# top_hk2.net
KiCad netlist of a schematic drawn in EAGLE
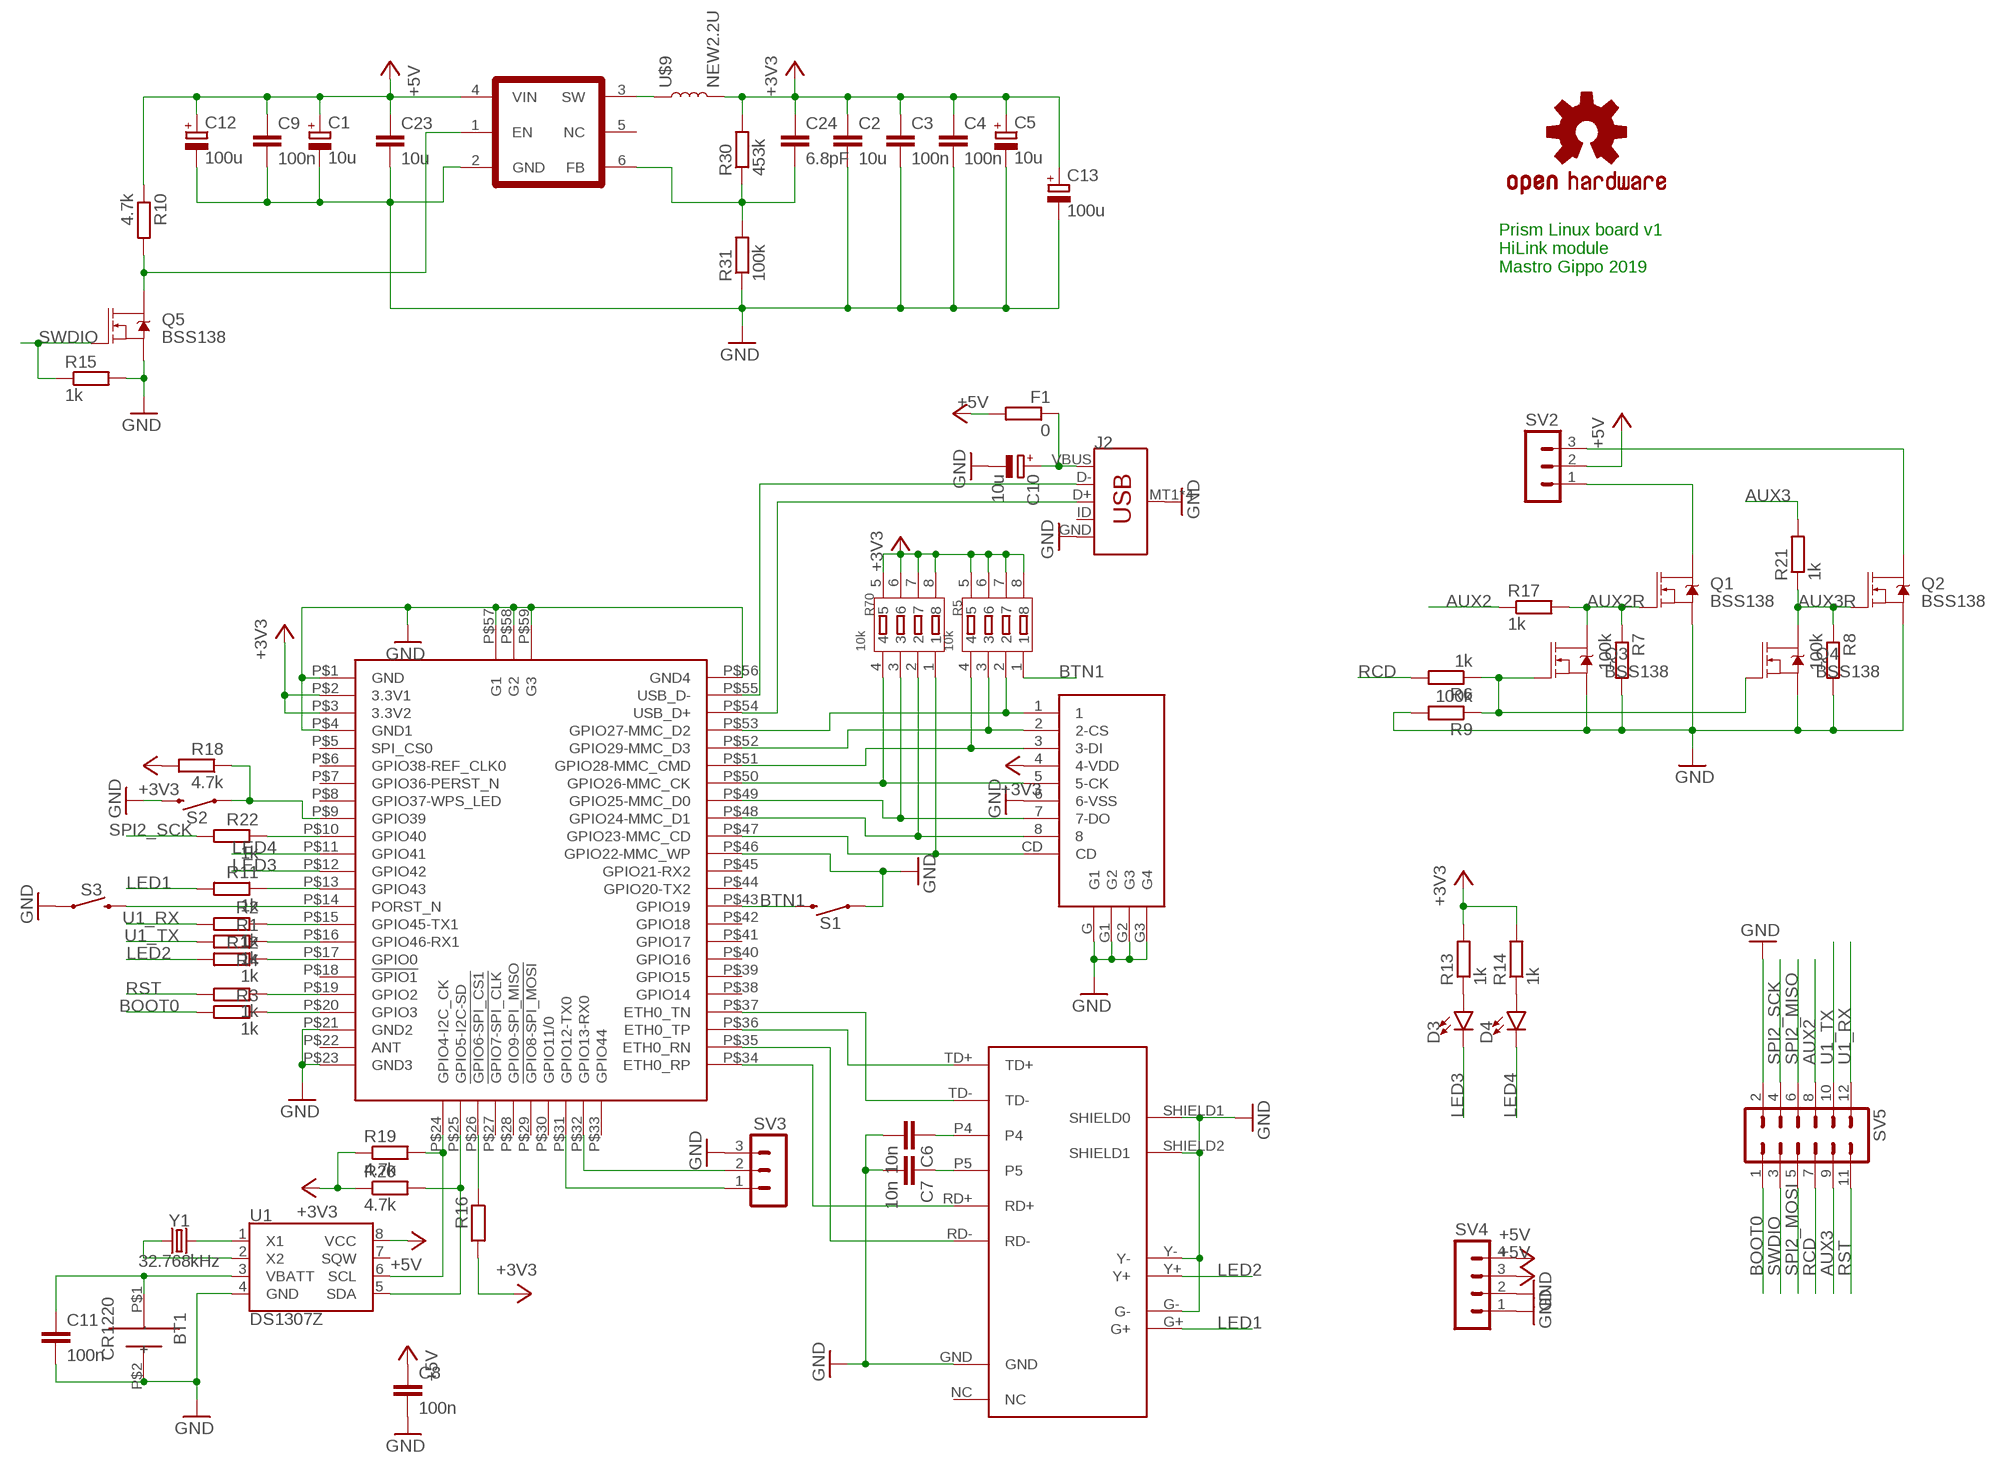
[diagram p0: schematic, sheet 1]

(export (version "E")
  (design (tool "Eeschema 10.0.6"))
  (components
    (comp (ref "BT1")
      (value "CR1220")
      (footprint "eagle-import:CR1220")
      (libsource (lib "eagle-import") (part "CR1220"))
    )
    (comp (ref "C1")
      (value "10u")
      (footprint "eagle-import:B_3528-21R")
      (libsource (lib "eagle-import") (part "CPOL-EUB/3528-21R"))
    )
    (comp (ref "C2")
      (value "10u")
      (footprint "eagle-import:C0805K")
      (libsource (lib "eagle-import") (part "C-EUC0805K"))
    )
    (comp (ref "C3")
      (value "100n")
      (footprint "eagle-import:C0805K")
      (libsource (lib "eagle-import") (part "C-EUC0805K"))
    )
    (comp (ref "C4")
      (value "100n")
      (footprint "eagle-import:C0805K")
      (libsource (lib "eagle-import") (part "C-EUC0805K"))
    )
    (comp (ref "C5")
      (value "10u")
      (footprint "eagle-import:B_3528-21R")
      (libsource (lib "eagle-import") (part "CPOL-EUB/3528-21R"))
    )
    (comp (ref "C6")
      (value "10n")
      (footprint "eagle-import:C0805K")
      (libsource (lib "eagle-import") (part "C-EUC0805K"))
    )
    (comp (ref "C7")
      (value "10n")
      (footprint "eagle-import:C0805K")
      (libsource (lib "eagle-import") (part "C-EUC0805K"))
    )
    (comp (ref "C8")
      (value "100n")
      (footprint "eagle-import:C0805K")
      (libsource (lib "eagle-import") (part "C-EUC0805K"))
    )
    (comp (ref "C9")
      (value "100n")
      (footprint "eagle-import:C0805K")
      (libsource (lib "eagle-import") (part "C-EUC0805K"))
    )
    (comp (ref "C10")
      (value "10u")
      (footprint "eagle-import:B_3528-21R")
      (libsource (lib "eagle-import") (part "CPOL-EUB/3528-21R"))
    )
    (comp (ref "C11")
      (value "100n")
      (footprint "eagle-import:C0805K")
      (libsource (lib "eagle-import") (part "C-EUC0805K"))
    )
    (comp (ref "C12")
      (value "100u")
      (footprint "eagle-import:153CLV-0505")
      (libsource (lib "eagle-import") (part "CPOL-EU153CLV-0505"))
    )
    (comp (ref "C13")
      (value "100u")
      (footprint "eagle-import:153CLV-0505")
      (libsource (lib "eagle-import") (part "CPOL-EU153CLV-0505"))
    )
    (comp (ref "C23")
      (value "10u")
      (footprint "eagle-import:C0805K")
      (libsource (lib "eagle-import") (part "C-EUC0805K"))
    )
    (comp (ref "C24")
      (value "6.8pF")
      (footprint "eagle-import:C0805K")
      (libsource (lib "eagle-import") (part "C-EUC0805K"))
    )
    (comp (ref "D3")
      (value "LED1206")
      (footprint "eagle-import:LED-1206")
      (libsource (lib "eagle-import") (part "LED1206"))
    )
    (comp (ref "D4")
      (value "LED1206")
      (footprint "eagle-import:LED-1206")
      (libsource (lib "eagle-import") (part "LED1206"))
    )
    (comp (ref "F1")
      (value "0")
      (footprint "eagle-import:R0603")
      (libsource (lib "eagle-import") (part "R-EU_R0603"))
    )
    (comp (ref "J2")
      (value "USB_MICRO-B_SMT")
      (footprint "eagle-import:USB-MICROB")
      (libsource (lib "eagle-import") (part "USB_MICRO-B_SMT"))
    )
    (comp (ref "Q1")
      (value "BSS138")
      (footprint "eagle-import:SOT23-3")
      (libsource (lib "eagle-import") (part "MOSFET-NCH-BSS138"))
    )
    (comp (ref "Q2")
      (value "BSS138")
      (footprint "eagle-import:SOT23-3")
      (libsource (lib "eagle-import") (part "MOSFET-NCH-BSS138"))
    )
    (comp (ref "Q3")
      (value "BSS138")
      (footprint "eagle-import:SOT23-3")
      (libsource (lib "eagle-import") (part "MOSFET-NCH-BSS138"))
    )
    (comp (ref "Q4")
      (value "BSS138")
      (footprint "eagle-import:SOT23-3")
      (libsource (lib "eagle-import") (part "MOSFET-NCH-BSS138"))
    )
    (comp (ref "Q5")
      (value "BSS138")
      (footprint "eagle-import:SOT23-3")
      (libsource (lib "eagle-import") (part "MOSFET-NCH-BSS138"))
    )
    (comp (ref "R1")
      (value "1k")
      (footprint "eagle-import:R0805")
      (libsource (lib "eagle-import") (part "R-EU_R0805"))
    )
    (comp (ref "R2")
      (value "1k")
      (footprint "eagle-import:R0805")
      (libsource (lib "eagle-import") (part "R-EU_R0805"))
    )
    (comp (ref "R3")
      (value "1k")
      (footprint "eagle-import:R0805")
      (libsource (lib "eagle-import") (part "R-EU_R0805"))
    )
    (comp (ref "R4")
      (value "1k")
      (footprint "eagle-import:R0805")
      (libsource (lib "eagle-import") (part "R-EU_R0805"))
    )
    (comp (ref "R5")
      (value "10k")
      (footprint "eagle-import:RA1206-8")
      (fields (field (name "MPN") "Chip-Array-Series-1%"))
      (libsource (lib "eagle-import") (part "SMD-RES-ARRAY-1K-4R(RA1206-8)"))
    )
    (comp (ref "R6")
      (value "1k")
      (footprint "eagle-import:R0805")
      (libsource (lib "eagle-import") (part "R-EU_R0805"))
    )
    (comp (ref "R7")
      (value "100k")
      (footprint "eagle-import:R0805")
      (libsource (lib "eagle-import") (part "R-EU_R0805"))
    )
    (comp (ref "R8")
      (value "100k")
      (footprint "eagle-import:R0805")
      (libsource (lib "eagle-import") (part "R-EU_R0805"))
    )
    (comp (ref "R9")
      (value "100k")
      (footprint "eagle-import:R0805")
      (libsource (lib "eagle-import") (part "R-EU_R0805"))
    )
    (comp (ref "R10")
      (value "4.7k")
      (footprint "eagle-import:R0805")
      (libsource (lib "eagle-import") (part "R-EU_R0805"))
    )
    (comp (ref "R11")
      (value "1k")
      (footprint "eagle-import:R0805")
      (libsource (lib "eagle-import") (part "R-EU_R0805"))
    )
    (comp (ref "R12")
      (value "1k")
      (footprint "eagle-import:R0805")
      (libsource (lib "eagle-import") (part "R-EU_R0805"))
    )
    (comp (ref "R13")
      (value "1k")
      (footprint "eagle-import:R0805")
      (libsource (lib "eagle-import") (part "R-EU_R0805"))
    )
    (comp (ref "R14")
      (value "1k")
      (footprint "eagle-import:R0805")
      (libsource (lib "eagle-import") (part "R-EU_R0805"))
    )
    (comp (ref "R15")
      (value "1k")
      (footprint "eagle-import:R0805")
      (libsource (lib "eagle-import") (part "R-EU_R0805"))
    )
    (comp (ref "R16")
      (value "R-EU_R0805")
      (footprint "eagle-import:R0805")
      (libsource (lib "eagle-import") (part "R-EU_R0805"))
    )
    (comp (ref "R17")
      (value "1k")
      (footprint "eagle-import:R0805")
      (libsource (lib "eagle-import") (part "R-EU_R0805"))
    )
    (comp (ref "R18")
      (value "4.7k")
      (footprint "eagle-import:R0805")
      (libsource (lib "eagle-import") (part "R-EU_R0805"))
    )
    (comp (ref "R19")
      (value "4.7k")
      (footprint "eagle-import:R0805")
      (libsource (lib "eagle-import") (part "R-EU_R0805"))
    )
    (comp (ref "R20")
      (value "4.7k")
      (footprint "eagle-import:R0805")
      (libsource (lib "eagle-import") (part "R-EU_R0805"))
    )
    (comp (ref "R21")
      (value "1k")
      (footprint "eagle-import:R0805")
      (libsource (lib "eagle-import") (part "R-EU_R0805"))
    )
    (comp (ref "R22")
      (value "1k")
      (footprint "eagle-import:R0805")
      (libsource (lib "eagle-import") (part "R-EU_R0805"))
    )
    (comp (ref "R30")
      (value "453k")
      (footprint "eagle-import:R0805")
      (libsource (lib "eagle-import") (part "R_EU"))
    )
    (comp (ref "R31")
      (value "100k")
      (footprint "eagle-import:R0805")
      (libsource (lib "eagle-import") (part "R_EU"))
    )
    (comp (ref "R70")
      (value "10k")
      (footprint "eagle-import:RA1206-8")
      (fields (field (name "MPN") "Chip-Array-Series-1%"))
      (libsource (lib "eagle-import") (part "SMD-RES-ARRAY-1K-4R(RA1206-8)"))
    )
    (comp (ref "S1")
      (value "MOMENTARY-SWITCH-SPST-SMD-6.0X3.5MM")
      (footprint "eagle-import:TACTILE_SWITCH_SMD_6.0X3.5MM")
      (libsource (lib "eagle-import") (part "MOMENTARY-SWITCH-SPST-SMD-6.0X3.5MM"))
    )
    (comp (ref "S2")
      (value "MOMENTARY-SWITCH-SPST-SMD-6.0X3.5MM")
      (footprint "eagle-import:TACTILE_SWITCH_SMD_6.0X3.5MM")
      (libsource (lib "eagle-import") (part "MOMENTARY-SWITCH-SPST-SMD-6.0X3.5MM"))
    )
    (comp (ref "S3")
      (value "MOMENTARY-SWITCH-SPST-PTH-RIGHT-ANGLE")
      (footprint "eagle-import:TACTILE_SWITCH_PTH_RIGHT_ANGLE")
      (libsource (lib "eagle-import") (part "MOMENTARY-SWITCH-SPST-PTH-RIGHT-ANGLE"))
    )
    (comp (ref "SV2")
      (value "MA03-1")
      (footprint "eagle-import:MA03-1")
      (libsource (lib "eagle-import") (part "MA03-1"))
    )
    (comp (ref "SV3")
      (value "MA03-1")
      (footprint "eagle-import:MA03-1")
      (libsource (lib "eagle-import") (part "MA03-1"))
    )
    (comp (ref "SV4")
      (value "MA04-1")
      (footprint "eagle-import:MA04-1")
      (libsource (lib "eagle-import") (part "MA04-1"))
    )
    (comp (ref "SV5")
      (value "MA06-2")
      (footprint "eagle-import:MA06-2")
      (libsource (lib "eagle-import") (part "MA06-2"))
    )
    (comp (ref "U$1")
      (value "OSHW-LOGOS")
      (footprint "eagle-import:OSHW-LOGO-S")
      (libsource (lib "eagle-import") (part "OSHW-LOGOS"))
    )
    (comp (ref "U$2")
      (value "HLK-7688A")
      (footprint "eagle-import:HLK-7688A")
      (libsource (lib "eagle-import") (part "HLK-7688A"))
    )
    (comp (ref "U$3")
      (value "MICRO_SD")
      (footprint "eagle-import:MICRO_SD_C")
      (libsource (lib "eagle-import") (part "MICRO_SD"))
    )
    (comp (ref "U$4")
      (value "HR911105A")
      (footprint "eagle-import:RJ45")
      (libsource (lib "eagle-import") (part "HR911105A"))
    )
    (comp (ref "U$8")
      (value "TLV62658")
      (footprint "eagle-import:SOT23-6")
      (libsource (lib "eagle-import") (part "TLV62658"))
    )
    (comp (ref "U$9")
      (value "NEW2.2U")
      (footprint "eagle-import:INDUCTOR_4X4MM")
      (libsource (lib "eagle-import") (part "NEW2.2U"))
    )
    (comp (ref "U1")
      (value "DS1307Z")
      (footprint "eagle-import:SO08-0.15")
      (libsource (lib "eagle-import") (part "DS1307Z"))
    )
    (comp (ref "Y1")
      (value "32.768kHz")
      (footprint "eagle-import:CRYSTAL-SMD-2X6-CYL")
      (libsource (lib "eagle-import") (part "CRYSTAL-32.768KHZSMD-2X6"))
    )
  )
  (nets
    (net (code "1") (name "+3V3") (class "Default")
      (node (ref "C13") (pin "+") (pinfunction "+_+") (pintype "passive"))
      (node (ref "C2") (pin "1") (pinfunction "1_1") (pintype "passive"))
      (node (ref "C24") (pin "1") (pinfunction "1_1") (pintype "passive"))
      (node (ref "C3") (pin "1") (pinfunction "1_1") (pintype "passive"))
      (node (ref "C4") (pin "1") (pinfunction "1_1") (pintype "passive"))
      (node (ref "C5") (pin "+") (pinfunction "+_+") (pintype "passive"))
      (node (ref "R13") (pin "2") (pinfunction "2_2") (pintype "passive"))
      (node (ref "R14") (pin "2") (pinfunction "2_2") (pintype "passive"))
      (node (ref "R16") (pin "2") (pinfunction "2_2") (pintype "passive"))
      (node (ref "R18") (pin "2") (pinfunction "2_2") (pintype "passive"))
      (node (ref "R19") (pin "1") (pinfunction "1_1") (pintype "passive"))
      (node (ref "R20") (pin "1") (pinfunction "1_1") (pintype "passive"))
      (node (ref "R30") (pin "2") (pinfunction "2_2") (pintype "passive"))
      (node (ref "R5") (pin "5") (pinfunction "5_5") (pintype "bidirectional"))
      (node (ref "R5") (pin "6") (pinfunction "6_6") (pintype "bidirectional"))
      (node (ref "R5") (pin "7") (pinfunction "7_7") (pintype "bidirectional"))
      (node (ref "R5") (pin "8") (pinfunction "8_8") (pintype "bidirectional"))
      (node (ref "R70") (pin "5") (pinfunction "5_5") (pintype "bidirectional"))
      (node (ref "R70") (pin "6") (pinfunction "6_6") (pintype "bidirectional"))
      (node (ref "R70") (pin "7") (pinfunction "7_7") (pintype "bidirectional"))
      (node (ref "R70") (pin "8") (pinfunction "8_8") (pintype "bidirectional"))
      (node (ref "U$2") (pin "P$2") (pinfunction "3.3V1_P$2") (pintype "bidirectional"))
      (node (ref "U$2") (pin "P$3") (pinfunction "3.3V2_P$3") (pintype "bidirectional"))
      (node (ref "U$3") (pin "4") (pinfunction "4-VDD_4") (pintype "bidirectional"))
      (node (ref "U$9") (pin "P$2") (pinfunction "2_P$2") (pintype "passive"))
    )
    (net (code "2") (name "+5V") (class "Default")
      (node (ref "C1") (pin "+") (pinfunction "+_+") (pintype "passive"))
      (node (ref "C12") (pin "+") (pinfunction "+_+") (pintype "passive"))
      (node (ref "C23") (pin "1") (pinfunction "1_1") (pintype "passive"))
      (node (ref "C8") (pin "1") (pinfunction "1_1") (pintype "passive"))
      (node (ref "C9") (pin "1") (pinfunction "1_1") (pintype "passive"))
      (node (ref "F1") (pin "2") (pinfunction "2_2") (pintype "passive"))
      (node (ref "R10") (pin "1") (pinfunction "1_1") (pintype "passive"))
      (node (ref "SV2") (pin "2") (pinfunction "2_2") (pintype "passive"))
      (node (ref "SV4") (pin "3") (pinfunction "3_3") (pintype "passive"))
      (node (ref "SV4") (pin "4") (pinfunction "4_4") (pintype "passive"))
      (node (ref "U$8") (pin "4") (pinfunction "VIN_4") (pintype "bidirectional"))
      (node (ref "U1") (pin "8") (pinfunction "VCC_8") (pintype "bidirectional"))
    )
    (net (code "3") (name "/AUX2") (class "Default")
      (node (ref "R17") (pin "1") (pinfunction "1_1") (pintype "passive"))
      (node (ref "SV5") (pin "8") (pinfunction "8_8") (pintype "passive"))
    )
    (net (code "4") (name "/AUX2R") (class "Default")
      (node (ref "Q1") (pin "1") (pinfunction "G_1") (pintype "bidirectional"))
      (node (ref "Q3") (pin "3") (pinfunction "D_3") (pintype "bidirectional"))
      (node (ref "R17") (pin "2") (pinfunction "2_2") (pintype "passive"))
      (node (ref "R7") (pin "1") (pinfunction "1_1") (pintype "passive"))
    )
    (net (code "5") (name "/AUX3") (class "Default")
      (node (ref "R21") (pin "2") (pinfunction "2_2") (pintype "passive"))
      (node (ref "SV5") (pin "9") (pinfunction "9_9") (pintype "passive"))
    )
    (net (code "6") (name "/AUX3R") (class "Default")
      (node (ref "Q2") (pin "1") (pinfunction "G_1") (pintype "bidirectional"))
      (node (ref "Q4") (pin "3") (pinfunction "D_3") (pintype "bidirectional"))
      (node (ref "R21") (pin "1") (pinfunction "1_1") (pintype "passive"))
      (node (ref "R8") (pin "1") (pinfunction "1_1") (pintype "passive"))
    )
    (net (code "7") (name "/BOOT0") (class "Default")
      (node (ref "R3") (pin "2") (pinfunction "2_2") (pintype "passive"))
      (node (ref "SV5") (pin "1") (pinfunction "1_1") (pintype "passive"))
    )
    (net (code "8") (name "/BTN1") (class "Default")
      (node (ref "R5") (pin "1") (pinfunction "1_1") (pintype "bidirectional"))
      (node (ref "S1") (pin "2") (pinfunction "2_2") (pintype "passive"))
      (node (ref "U$2") (pin "P$43") (pinfunction "GPIO19_P$43") (pintype "bidirectional"))
    )
    (net (code "9") (name "/LED1") (class "Default")
      (node (ref "R11") (pin "2") (pinfunction "2_2") (pintype "passive"))
      (node (ref "U$4") (pin "G+") (pinfunction "G+_G+") (pintype "bidirectional"))
    )
    (net (code "10") (name "/LED2") (class "Default")
      (node (ref "R12") (pin "2") (pinfunction "2_2") (pintype "passive"))
      (node (ref "U$4") (pin "Y+") (pinfunction "Y+_Y+") (pintype "bidirectional"))
    )
    (net (code "11") (name "/LED3") (class "Default")
      (node (ref "D3") (pin "C") (pinfunction "C_C") (pintype "passive"))
      (node (ref "U$2") (pin "P$12") (pinfunction "GPIO42_P$12") (pintype "bidirectional"))
    )
    (net (code "12") (name "/LED4") (class "Default")
      (node (ref "D4") (pin "C") (pinfunction "C_C") (pintype "passive"))
      (node (ref "U$2") (pin "P$11") (pinfunction "GPIO41_P$11") (pintype "bidirectional"))
    )
    (net (code "13") (name "/RCD") (class "Default")
      (node (ref "R6") (pin "2") (pinfunction "2_2") (pintype "passive"))
      (node (ref "SV5") (pin "7") (pinfunction "7_7") (pintype "passive"))
    )
    (net (code "14") (name "/RST") (class "Default")
      (node (ref "R4") (pin "2") (pinfunction "2_2") (pintype "passive"))
      (node (ref "SV5") (pin "11") (pinfunction "11_11") (pintype "passive"))
    )
    (net (code "15") (name "/SPI2_MISO") (class "Default")
      (node (ref "SV5") (pin "6") (pinfunction "6_6") (pintype "passive"))
    )
    (net (code "16") (name "/SPI2_MOSI") (class "Default")
      (node (ref "SV5") (pin "5") (pinfunction "5_5") (pintype "passive"))
    )
    (net (code "17") (name "/SPI2_SCK") (class "Default")
      (node (ref "R22") (pin "2") (pinfunction "2_2") (pintype "passive"))
      (node (ref "SV5") (pin "4") (pinfunction "4_4") (pintype "passive"))
    )
    (net (code "18") (name "/SWDIO") (class "Default")
      (node (ref "Q5") (pin "1") (pinfunction "G_1") (pintype "bidirectional"))
      (node (ref "R15") (pin "1") (pinfunction "1_1") (pintype "passive"))
      (node (ref "SV5") (pin "3") (pinfunction "3_3") (pintype "passive"))
    )
    (net (code "19") (name "/U1_RX") (class "Default")
      (node (ref "R2") (pin "2") (pinfunction "2_2") (pintype "passive"))
      (node (ref "SV5") (pin "12") (pinfunction "12_12") (pintype "passive"))
    )
    (net (code "20") (name "/U1_TX") (class "Default")
      (node (ref "R1") (pin "2") (pinfunction "2_2") (pintype "passive"))
      (node (ref "SV5") (pin "10") (pinfunction "10_10") (pintype "passive"))
    )
    (net (code "21") (name "GND") (class "Default")
      (node (ref "BT1") (pin "P$2") (pinfunction "-_P$2") (pintype "power_in"))
      (node (ref "C1") (pin "-") (pinfunction "-_-") (pintype "passive"))
      (node (ref "C10") (pin "-") (pinfunction "-_-") (pintype "passive"))
      (node (ref "C11") (pin "2") (pinfunction "2_2") (pintype "passive"))
      (node (ref "C12") (pin "-") (pinfunction "-_-") (pintype "passive"))
      (node (ref "C13") (pin "-") (pinfunction "-_-") (pintype "passive"))
      (node (ref "C2") (pin "2") (pinfunction "2_2") (pintype "passive"))
      (node (ref "C23") (pin "2") (pinfunction "2_2") (pintype "passive"))
      (node (ref "C3") (pin "2") (pinfunction "2_2") (pintype "passive"))
      (node (ref "C4") (pin "2") (pinfunction "2_2") (pintype "passive"))
      (node (ref "C5") (pin "-") (pinfunction "-_-") (pintype "passive"))
      (node (ref "C6") (pin "2") (pinfunction "2_2") (pintype "passive"))
      (node (ref "C7") (pin "2") (pinfunction "2_2") (pintype "passive"))
      (node (ref "C8") (pin "2") (pinfunction "2_2") (pintype "passive"))
      (node (ref "C9") (pin "2") (pinfunction "2_2") (pintype "passive"))
      (node (ref "J2") (pin "GND") (pinfunction "GND_GND") (pintype "power_in"))
      (node (ref "J2") (pin "MT1") (pinfunction "SHIELD_MT1") (pintype "bidirectional"))
      (node (ref "J2") (pin "MT2") (pinfunction "SHIELD_MT2") (pintype "bidirectional"))
      (node (ref "J2") (pin "P$1") (pinfunction "SHIELD_P$1") (pintype "bidirectional"))
      (node (ref "J2") (pin "P$2") (pinfunction "SHIELD_P$2") (pintype "bidirectional"))
      (node (ref "Q1") (pin "2") (pinfunction "S_2") (pintype "bidirectional"))
      (node (ref "Q2") (pin "2") (pinfunction "S_2") (pintype "bidirectional"))
      (node (ref "Q3") (pin "2") (pinfunction "S_2") (pintype "bidirectional"))
      (node (ref "Q4") (pin "2") (pinfunction "S_2") (pintype "bidirectional"))
      (node (ref "Q5") (pin "2") (pinfunction "S_2") (pintype "bidirectional"))
      (node (ref "R15") (pin "2") (pinfunction "2_2") (pintype "passive"))
      (node (ref "R31") (pin "1") (pinfunction "1_1") (pintype "passive"))
      (node (ref "R7") (pin "2") (pinfunction "2_2") (pintype "passive"))
      (node (ref "R8") (pin "2") (pinfunction "2_2") (pintype "passive"))
      (node (ref "R9") (pin "2") (pinfunction "2_2") (pintype "passive"))
      (node (ref "S1") (pin "1") (pinfunction "1_1") (pintype "passive"))
      (node (ref "S2") (pin "2") (pinfunction "2_2") (pintype "passive"))
      (node (ref "S3") (pin "1") (pinfunction "1_1") (pintype "passive"))
      (node (ref "SV3") (pin "3") (pinfunction "3_3") (pintype "passive"))
      (node (ref "SV4") (pin "1") (pinfunction "1_1") (pintype "passive"))
      (node (ref "SV4") (pin "2") (pinfunction "2_2") (pintype "passive"))
      (node (ref "SV5") (pin "2") (pinfunction "2_2") (pintype "passive"))
      (node (ref "U$2") (pin "P$1") (pinfunction "GND_P$1") (pintype "bidirectional"))
      (node (ref "U$2") (pin "P$21") (pinfunction "GND2_P$21") (pintype "bidirectional"))
      (node (ref "U$2") (pin "P$23") (pinfunction "GND3_P$23") (pintype "bidirectional"))
      (node (ref "U$2") (pin "P$4") (pinfunction "GND1_P$4") (pintype "bidirectional"))
      (node (ref "U$2") (pin "P$46") (pinfunction "GPIO22-MMC_WP_P$46") (pintype "bidirectional"))
      (node (ref "U$2") (pin "P$56") (pinfunction "GND4_P$56") (pintype "bidirectional"))
      (node (ref "U$2") (pin "P$57") (pinfunction "G1_P$57") (pintype "bidirectional"))
      (node (ref "U$2") (pin "P$58") (pinfunction "G2_P$58") (pintype "bidirectional"))
      (node (ref "U$2") (pin "P$59") (pinfunction "G3_P$59") (pintype "bidirectional"))
      (node (ref "U$3") (pin "6") (pinfunction "6-VSS_6") (pintype "bidirectional"))
      (node (ref "U$3") (pin "G") (pinfunction "G1_G") (pintype "bidirectional"))
      (node (ref "U$3") (pin "G1") (pinfunction "G2_G1") (pintype "bidirectional"))
      (node (ref "U$3") (pin "G2") (pinfunction "G3_G2") (pintype "bidirectional"))
      (node (ref "U$3") (pin "G3") (pinfunction "G4_G3") (pintype "bidirectional"))
      (node (ref "U$4") (pin "G-") (pinfunction "G-_G-") (pintype "bidirectional"))
      (node (ref "U$4") (pin "GND") (pinfunction "GND_GND") (pintype "bidirectional"))
      (node (ref "U$4") (pin "SHIELD1") (pinfunction "SHIELD0_SHIELD1") (pintype "bidirectional"))
      (node (ref "U$4") (pin "SHIELD2") (pinfunction "SHIELD1_SHIELD2") (pintype "bidirectional"))
      (node (ref "U$4") (pin "Y-") (pinfunction "Y-_Y-") (pintype "bidirectional"))
      (node (ref "U$8") (pin "2") (pinfunction "GND_2") (pintype "bidirectional"))
      (node (ref "U1") (pin "4") (pinfunction "GND_4") (pintype "bidirectional"))
    )
    (net (code "22") (name "Net-(BT1-+)") (class "Default")
      (node (ref "BT1") (pin "P$1") (pinfunction "+_P$1") (pintype "power_in"))
      (node (ref "C11") (pin "1") (pinfunction "1_1") (pintype "passive"))
      (node (ref "U1") (pin "3") (pinfunction "VBATT_3") (pintype "bidirectional"))
    )
    (net (code "23") (name "Net-(C6-Pad1)") (class "Default")
      (node (ref "C6") (pin "1") (pinfunction "1_1") (pintype "passive"))
      (node (ref "U$4") (pin "P4") (pinfunction "P4_P4") (pintype "bidirectional"))
    )
    (net (code "24") (name "Net-(C7-Pad1)") (class "Default")
      (node (ref "C7") (pin "1") (pinfunction "1_1") (pintype "passive"))
      (node (ref "U$4") (pin "P5") (pinfunction "P5_P5") (pintype "bidirectional"))
    )
    (net (code "25") (name "Net-(C10-Pad+)") (class "Default")
      (node (ref "C10") (pin "+") (pinfunction "+_+") (pintype "passive"))
      (node (ref "F1") (pin "1") (pinfunction "1_1") (pintype "passive"))
      (node (ref "J2") (pin "VBUS") (pinfunction "VBUS_VBUS") (pintype "power_in"))
    )
    (net (code "26") (name "Net-(D3-PadA)") (class "Default")
      (node (ref "D3") (pin "A") (pinfunction "A_A") (pintype "passive"))
      (node (ref "R13") (pin "1") (pinfunction "1_1") (pintype "passive"))
    )
    (net (code "27") (name "Net-(D4-PadA)") (class "Default")
      (node (ref "D4") (pin "A") (pinfunction "A_A") (pintype "passive"))
      (node (ref "R14") (pin "1") (pinfunction "1_1") (pintype "passive"))
    )
    (net (code "28") (name "Net-(Q1-D)") (class "Default")
      (node (ref "Q1") (pin "3") (pinfunction "D_3") (pintype "bidirectional"))
      (node (ref "SV2") (pin "1") (pinfunction "1_1") (pintype "passive"))
    )
    (net (code "29") (name "Net-(Q2-D)") (class "Default")
      (node (ref "Q2") (pin "3") (pinfunction "D_3") (pintype "bidirectional"))
      (node (ref "SV2") (pin "3") (pinfunction "3_3") (pintype "passive"))
    )
    (net (code "30") (name "Net-(Q3-G)") (class "Default")
      (node (ref "Q3") (pin "1") (pinfunction "G_1") (pintype "bidirectional"))
      (node (ref "Q4") (pin "1") (pinfunction "G_1") (pintype "bidirectional"))
      (node (ref "R6") (pin "1") (pinfunction "1_1") (pintype "passive"))
      (node (ref "R9") (pin "1") (pinfunction "1_1") (pintype "passive"))
    )
    (net (code "31") (name "Net-(Q5-D)") (class "Default")
      (node (ref "Q5") (pin "3") (pinfunction "D_3") (pintype "bidirectional"))
      (node (ref "R10") (pin "2") (pinfunction "2_2") (pintype "passive"))
      (node (ref "U$8") (pin "1") (pinfunction "EN_1") (pintype "bidirectional"))
    )
    (net (code "32") (name "Net-(U$2-ETH0_RN)") (class "Default")
      (node (ref "U$2") (pin "P$35") (pinfunction "ETH0_RN_P$35") (pintype "bidirectional"))
      (node (ref "U$4") (pin "RD-") (pinfunction "RD-_RD-") (pintype "bidirectional"))
    )
    (net (code "33") (name "Net-(U$2-ETH0_RP)") (class "Default")
      (node (ref "U$2") (pin "P$34") (pinfunction "ETH0_RP_P$34") (pintype "bidirectional"))
      (node (ref "U$4") (pin "RD+") (pinfunction "RD+_RD+") (pintype "bidirectional"))
    )
    (net (code "34") (name "Net-(U$2-ETH0_TN)") (class "Default")
      (node (ref "U$2") (pin "P$37") (pinfunction "ETH0_TN_P$37") (pintype "bidirectional"))
      (node (ref "U$4") (pin "TD-") (pinfunction "TD-_TD-") (pintype "bidirectional"))
    )
    (net (code "35") (name "Net-(U$2-ETH0_TP)") (class "Default")
      (node (ref "U$2") (pin "P$36") (pinfunction "ETH0_TP_P$36") (pintype "bidirectional"))
      (node (ref "U$4") (pin "TD+") (pinfunction "TD+_TD+") (pintype "bidirectional"))
    )
    (net (code "36") (name "Net-(U$2-GPIO0)") (class "Default")
      (node (ref "R12") (pin "1") (pinfunction "1_1") (pintype "passive"))
      (node (ref "U$2") (pin "P$17") (pinfunction "GPIO0_P$17") (pintype "bidirectional"))
    )
    (net (code "37") (name "Net-(U$2-GPIO2)") (class "Default")
      (node (ref "R4") (pin "1") (pinfunction "1_1") (pintype "passive"))
      (node (ref "U$2") (pin "P$19") (pinfunction "GPIO2_P$19") (pintype "bidirectional"))
    )
    (net (code "38") (name "Net-(U$2-GPIO3)") (class "Default")
      (node (ref "R3") (pin "1") (pinfunction "1_1") (pintype "passive"))
      (node (ref "U$2") (pin "P$20") (pinfunction "GPIO3_P$20") (pintype "bidirectional"))
    )
    (net (code "39") (name "Net-(U$2-GPIO4-I2C_CK)") (class "Default")
      (node (ref "R19") (pin "2") (pinfunction "2_2") (pintype "passive"))
      (node (ref "U$2") (pin "P$24") (pinfunction "GPIO4-I2C_CK_P$24") (pintype "bidirectional"))
      (node (ref "U1") (pin "6") (pinfunction "SCL_6") (pintype "bidirectional"))
    )
    (net (code "40") (name "Net-(U$2-GPIO5-I2C-SD)") (class "Default")
      (node (ref "R20") (pin "2") (pinfunction "2_2") (pintype "passive"))
      (node (ref "U$2") (pin "P$25") (pinfunction "GPIO5-I2C-SD_P$25") (pintype "bidirectional"))
      (node (ref "U1") (pin "5") (pinfunction "SDA_5") (pintype "bidirectional"))
    )
    (net (code "41") (name "Net-(U$2-GPIO12-TX0)") (class "Default")
      (node (ref "SV3") (pin "1") (pinfunction "1_1") (pintype "passive"))
      (node (ref "U$2") (pin "P$31") (pinfunction "GPIO12-TX0_P$31") (pintype "bidirectional"))
    )
    (net (code "42") (name "Net-(U$2-GPIO13-RX0)") (class "Default")
      (node (ref "SV3") (pin "2") (pinfunction "2_2") (pintype "passive"))
      (node (ref "U$2") (pin "P$32") (pinfunction "GPIO13-RX0_P$32") (pintype "bidirectional"))
    )
    (net (code "43") (name "Net-(U$2-GPIO23-MMC_CD)") (class "Default")
      (node (ref "R70") (pin "1") (pinfunction "1_1") (pintype "bidirectional"))
      (node (ref "U$2") (pin "P$47") (pinfunction "GPIO23-MMC_CD_P$47") (pintype "bidirectional"))
      (node (ref "U$3") (pin "CD") (pinfunction "CD_CD") (pintype "bidirectional"))
    )
    (net (code "44") (name "Net-(U$2-GPIO24-MMC_D1)") (class "Default")
      (node (ref "R70") (pin "2") (pinfunction "2_2") (pintype "bidirectional"))
      (node (ref "U$2") (pin "P$48") (pinfunction "GPIO24-MMC_D1_P$48") (pintype "bidirectional"))
      (node (ref "U$3") (pin "8") (pinfunction "8_8") (pintype "bidirectional"))
    )
    (net (code "45") (name "Net-(U$2-GPIO25-MMC_D0)") (class "Default")
      (node (ref "R70") (pin "3") (pinfunction "3_3") (pintype "bidirectional"))
      (node (ref "U$2") (pin "P$49") (pinfunction "GPIO25-MMC_D0_P$49") (pintype "bidirectional"))
      (node (ref "U$3") (pin "7") (pinfunction "7-DO_7") (pintype "bidirectional"))
    )
    (net (code "46") (name "Net-(U$2-GPIO26-MMC_CK)") (class "Default")
      (node (ref "R70") (pin "4") (pinfunction "4_4") (pintype "bidirectional"))
      (node (ref "U$2") (pin "P$50") (pinfunction "GPIO26-MMC_CK_P$50") (pintype "bidirectional"))
      (node (ref "U$3") (pin "5") (pinfunction "5-CK_5") (pintype "bidirectional"))
    )
    (net (code "47") (name "Net-(U$2-GPIO27-MMC_D2)") (class "Default")
      (node (ref "R5") (pin "2") (pinfunction "2_2") (pintype "bidirectional"))
      (node (ref "U$2") (pin "P$53") (pinfunction "GPIO27-MMC_D2_P$53") (pintype "bidirectional"))
      (node (ref "U$3") (pin "1") (pinfunction "1_1") (pintype "bidirectional"))
    )
    (net (code "48") (name "Net-(U$2-GPIO28-MMC_CMD)") (class "Default")
      (node (ref "R5") (pin "4") (pinfunction "4_4") (pintype "bidirectional"))
      (node (ref "U$2") (pin "P$51") (pinfunction "GPIO28-MMC_CMD_P$51") (pintype "bidirectional"))
      (node (ref "U$3") (pin "3") (pinfunction "3-DI_3") (pintype "bidirectional"))
    )
    (net (code "49") (name "Net-(U$2-GPIO29-MMC_D3)") (class "Default")
      (node (ref "R5") (pin "3") (pinfunction "3_3") (pintype "bidirectional"))
      (node (ref "U$2") (pin "P$52") (pinfunction "GPIO29-MMC_D3_P$52") (pintype "bidirectional"))
      (node (ref "U$3") (pin "2") (pinfunction "2-CS_2") (pintype "bidirectional"))
    )
    (net (code "50") (name "Net-(U$2-GPIO39)") (class "Default")
      (node (ref "R18") (pin "1") (pinfunction "1_1") (pintype "passive"))
      (node (ref "S2") (pin "1") (pinfunction "1_1") (pintype "passive"))
      (node (ref "U$2") (pin "P$9") (pinfunction "GPIO39_P$9") (pintype "bidirectional"))
    )
    (net (code "51") (name "Net-(U$2-GPIO40)") (class "Default")
      (node (ref "R22") (pin "1") (pinfunction "1_1") (pintype "passive"))
      (node (ref "U$2") (pin "P$10") (pinfunction "GPIO40_P$10") (pintype "bidirectional"))
    )
    (net (code "52") (name "Net-(U$2-GPIO43)") (class "Default")
      (node (ref "R11") (pin "1") (pinfunction "1_1") (pintype "passive"))
      (node (ref "U$2") (pin "P$13") (pinfunction "GPIO43_P$13") (pintype "bidirectional"))
    )
    (net (code "53") (name "Net-(U$2-GPIO45-TX1)") (class "Default")
      (node (ref "R2") (pin "1") (pinfunction "1_1") (pintype "passive"))
      (node (ref "U$2") (pin "P$15") (pinfunction "GPIO45-TX1_P$15") (pintype "bidirectional"))
    )
    (net (code "54") (name "Net-(U$2-GPIO46-RX1)") (class "Default")
      (node (ref "R1") (pin "1") (pinfunction "1_1") (pintype "passive"))
      (node (ref "U$2") (pin "P$16") (pinfunction "GPIO46-RX1_P$16") (pintype "bidirectional"))
    )
    (net (code "55") (name "Net-(U$2-PORST_N)") (class "Default")
      (node (ref "S3") (pin "2") (pinfunction "2_2") (pintype "passive"))
      (node (ref "U$2") (pin "P$14") (pinfunction "PORST_N_P$14") (pintype "bidirectional"))
    )
    (net (code "56") (name "Net-(U$2-USB_D+)") (class "Default")
      (node (ref "J2") (pin "D+") (pinfunction "D+_D+") (pintype "bidirectional"))
      (node (ref "U$2") (pin "P$54") (pinfunction "USB_D+_P$54") (pintype "bidirectional"))
    )
    (net (code "57") (name "Net-(U$2-USB_D-)") (class "Default")
      (node (ref "J2") (pin "D-") (pinfunction "D-_D-") (pintype "bidirectional"))
      (node (ref "U$2") (pin "P$55") (pinfunction "USB_D-_P$55") (pintype "bidirectional"))
    )
    (net (code "58") (name "Net-(U$2-~{GPIO6-SPI_CS1})") (class "Default")
      (node (ref "R16") (pin "1") (pinfunction "1_1") (pintype "passive"))
      (node (ref "U$2") (pin "P$26") (pinfunction "~{GPIO6-SPI_CS1}_P$26") (pintype "bidirectional"))
    )
    (net (code "59") (name "Net-(U$8-FB)") (class "Default")
      (node (ref "C24") (pin "2") (pinfunction "2_2") (pintype "passive"))
      (node (ref "R30") (pin "1") (pinfunction "1_1") (pintype "passive"))
      (node (ref "R31") (pin "2") (pinfunction "2_2") (pintype "passive"))
      (node (ref "U$8") (pin "6") (pinfunction "FB_6") (pintype "bidirectional"))
    )
    (net (code "60") (name "Net-(U$8-SW)") (class "Default")
      (node (ref "U$8") (pin "3") (pinfunction "SW_3") (pintype "bidirectional"))
      (node (ref "U$9") (pin "P$1") (pinfunction "1_P$1") (pintype "passive"))
    )
    (net (code "61") (name "Net-(U1-X1)") (class "Default")
      (node (ref "U1") (pin "1") (pinfunction "X1_1") (pintype "bidirectional"))
      (node (ref "Y1") (pin "X2") (pinfunction "2_X2") (pintype "passive"))
    )
    (net (code "62") (name "Net-(U1-X2)") (class "Default")
      (node (ref "U1") (pin "2") (pinfunction "X2_2") (pintype "bidirectional"))
      (node (ref "Y1") (pin "X1") (pinfunction "1_X1") (pintype "passive"))
    )
    (net (code "63") (name "unconnected-(J2-PadID)") (class "Default")
      (node (ref "J2") (pin "ID") (pinfunction "ID_ID") (pintype "bidirectional"))
    )
    (net (code "64") (name "unconnected-(U$2-ANT-PadP$22)") (class "Default")
      (node (ref "U$2") (pin "P$22") (pinfunction "ANT_P$22") (pintype "bidirectional"))
    )
    (net (code "65") (name "unconnected-(U$2-GPIO9-SPI_MISO-PadP$28)") (class "Default")
      (node (ref "U$2") (pin "P$28") (pinfunction "GPIO9-SPI_MISO_P$28") (pintype "bidirectional"))
    )
    (net (code "66") (name "unconnected-(U$2-GPIO11{slash}0-PadP$30)") (class "Default")
      (node (ref "U$2") (pin "P$30") (pinfunction "GPIO11/0_P$30") (pintype "bidirectional"))
    )
    (net (code "67") (name "unconnected-(U$2-GPIO14-PadP$38)") (class "Default")
      (node (ref "U$2") (pin "P$38") (pinfunction "GPIO14_P$38") (pintype "bidirectional"))
    )
    (net (code "68") (name "unconnected-(U$2-GPIO15-PadP$39)") (class "Default")
      (node (ref "U$2") (pin "P$39") (pinfunction "GPIO15_P$39") (pintype "bidirectional"))
    )
    (net (code "69") (name "unconnected-(U$2-GPIO16-PadP$40)") (class "Default")
      (node (ref "U$2") (pin "P$40") (pinfunction "GPIO16_P$40") (pintype "bidirectional"))
    )
    (net (code "70") (name "unconnected-(U$2-GPIO17-PadP$41)") (class "Default")
      (node (ref "U$2") (pin "P$41") (pinfunction "GPIO17_P$41") (pintype "bidirectional"))
    )
    (net (code "71") (name "unconnected-(U$2-GPIO18-PadP$42)") (class "Default")
      (node (ref "U$2") (pin "P$42") (pinfunction "GPIO18_P$42") (pintype "bidirectional"))
    )
    (net (code "72") (name "unconnected-(U$2-GPIO20-TX2-PadP$44)") (class "Default")
      (node (ref "U$2") (pin "P$44") (pinfunction "GPIO20-TX2_P$44") (pintype "bidirectional"))
    )
    (net (code "73") (name "unconnected-(U$2-GPIO21-RX2-PadP$45)") (class "Default")
      (node (ref "U$2") (pin "P$45") (pinfunction "GPIO21-RX2_P$45") (pintype "bidirectional"))
    )
    (net (code "74") (name "unconnected-(U$2-GPIO36-PERST_N-PadP$7)") (class "Default")
      (node (ref "U$2") (pin "P$7") (pinfunction "GPIO36-PERST_N_P$7") (pintype "bidirectional"))
    )
    (net (code "75") (name "unconnected-(U$2-GPIO37-WPS_LED-PadP$8)") (class "Default")
      (node (ref "U$2") (pin "P$8") (pinfunction "GPIO37-WPS_LED_P$8") (pintype "bidirectional"))
    )
    (net (code "76") (name "unconnected-(U$2-GPIO38-REF_CLK0-PadP$6)") (class "Default")
      (node (ref "U$2") (pin "P$6") (pinfunction "GPIO38-REF_CLK0_P$6") (pintype "bidirectional"))
    )
    (net (code "77") (name "unconnected-(U$2-GPIO44-PadP$33)") (class "Default")
      (node (ref "U$2") (pin "P$33") (pinfunction "GPIO44_P$33") (pintype "bidirectional"))
    )
    (net (code "78") (name "unconnected-(U$2-SPI_CS0-PadP$5)") (class "Default")
      (node (ref "U$2") (pin "P$5") (pinfunction "SPI_CS0_P$5") (pintype "bidirectional"))
    )
    (net (code "79") (name "unconnected-(U$2-~{GPIO1}-PadP$18)") (class "Default")
      (node (ref "U$2") (pin "P$18") (pinfunction "~{GPIO1}_P$18") (pintype "bidirectional"))
    )
    (net (code "80") (name "unconnected-(U$2-~{GPIO7-SPI_CLK}-PadP$27)") (class "Default")
      (node (ref "U$2") (pin "P$27") (pinfunction "~{GPIO7-SPI_CLK}_P$27") (pintype "bidirectional"))
    )
    (net (code "81") (name "unconnected-(U$2-~{GPIO8-SPI_MOSI}-PadP$29)") (class "Default")
      (node (ref "U$2") (pin "P$29") (pinfunction "~{GPIO8-SPI_MOSI}_P$29") (pintype "bidirectional"))
    )
    (net (code "82") (name "unconnected-(U$4-PadNC)") (class "Default")
      (node (ref "U$4") (pin "NC") (pinfunction "NC_NC") (pintype "bidirectional"))
    )
    (net (code "83") (name "unconnected-(U$8-NC-Pad5)") (class "Default")
      (node (ref "U$8") (pin "5") (pinfunction "NC_5") (pintype "bidirectional"))
    )
    (net (code "84") (name "unconnected-(U1-SQW-Pad7)") (class "Default")
      (node (ref "U1") (pin "7") (pinfunction "SQW_7") (pintype "bidirectional"))
    )
  )
)
